# connectors.net
KiCad netlist of a schematic drawn in Altium Designer
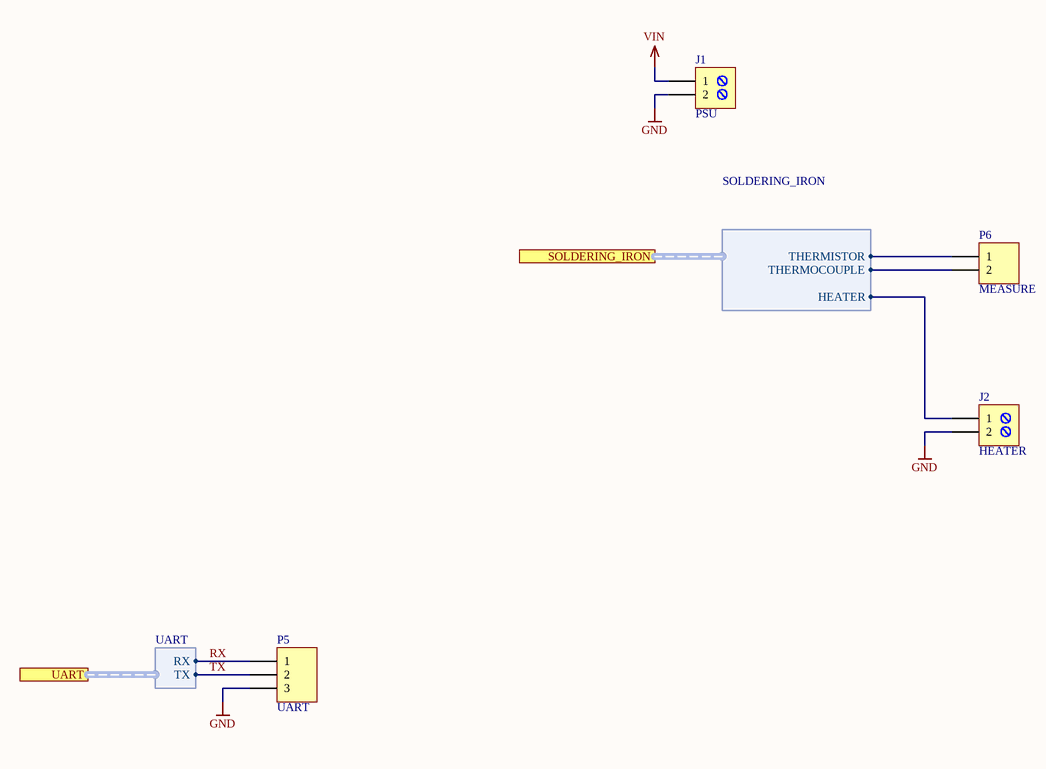
[diagram p0: connectors.SchDoc]

(export (version "E")
  (design (tool "Eeschema 10.0.6"))
  (components
    (comp (ref "J1")
      (value "PSU")
      (footprint "J_ARK2")
      (description "ARK Screw terminal, 2-Pin")
      (fields (field (name "PART NUMBER") "J_TB-5.0-P-2P") (field (name "MANUFACTURER") "DEGSON ELECTRONICS"))
      (libsource (lib "Library") (part "J_ARK2"))
    )
    (comp (ref "J2")
      (value "HEATER")
      (footprint "J_ARK2")
      (description "ARK Screw terminal, 2-Pin")
      (fields (field (name "PART NUMBER") "J_TB-5.0-P-2P") (field (name "MANUFACTURER") "DEGSON ELECTRONICS"))
      (libsource (lib "Library") (part "J_ARK2"))
    )
    (comp (ref "P5")
      (value "UART")
      (footprint "P_HEADER_1x3_2.54")
      (description "Header, 3-Pin")
      (fields (field (name "PART NUMBER") "P_HEADER_1x3_2.54") (field (name "MANUFACTURER") "Connfly"))
      (libsource (lib "Library") (part "P_HEADER_1x3"))
    )
    (comp (ref "P6")
      (value "MEASURE")
      (footprint "P_HEADER_1x2_2.54")
      (description "Header, 2-Pin")
      (fields (field (name "PART NUMBER") "P_HEADER_1x2_2.54") (field (name "MANUFACTURER") "Connfly"))
      (libsource (lib "Library") (part "P_HEADER_1x2"))
    )
  )
  (nets
    (net (code "3") (name "/HEATER") (class "Default")
      (node (ref "J2") (pin "1") (pinfunction "1_1") (pintype "passive"))
    )
    (net (code "4") (name "/RX") (class "Default")
      (node (ref "P5") (pin "1") (pinfunction "1_1") (pintype "passive"))
    )
    (net (code "5") (name "/THERMISTOR") (class "Default")
      (node (ref "P6") (pin "1") (pinfunction "1_1") (pintype "passive"))
    )
    (net (code "6") (name "/THERMOCOUPLE") (class "Default")
      (node (ref "P6") (pin "2") (pinfunction "2_2") (pintype "passive"))
    )
    (net (code "7") (name "/TX") (class "Default")
      (node (ref "P5") (pin "2") (pinfunction "2_2") (pintype "passive"))
    )
    (net (code "10") (name "GND") (class "Default")
      (node (ref "J1") (pin "2") (pinfunction "2_2") (pintype "passive"))
      (node (ref "J2") (pin "2") (pinfunction "2_2") (pintype "passive"))
      (node (ref "P5") (pin "3") (pinfunction "3_3") (pintype "passive"))
    )
    (net (code "11") (name "VIN") (class "Default")
      (node (ref "J1") (pin "1") (pinfunction "1_1") (pintype "passive"))
    )
  )
)
